# Sheet0-mcu.net
KiCad netlist of a schematic drawn in Altium Designer
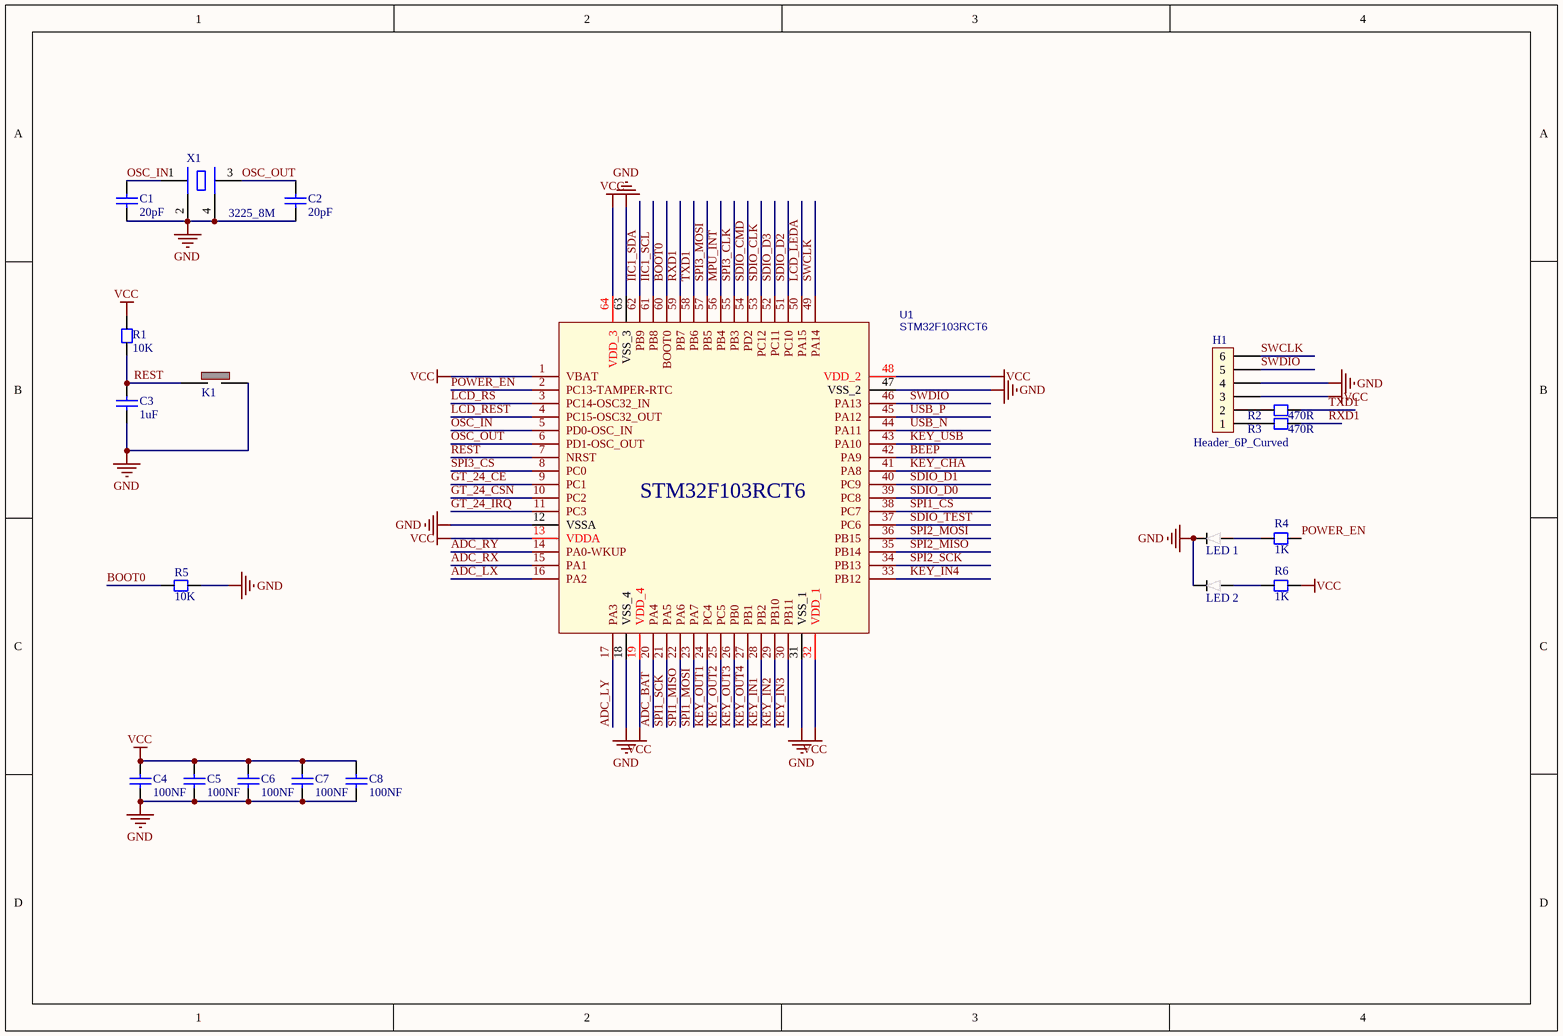
[diagram p0: Sheet0-mcu.SchDoc]

(export (version "E")
  (design (tool "Eeschema 10.0.6"))
  (components
    (comp (ref "C1")
      (value "20pF")
      (footprint "CC1608-0603")
      (description "0603封装的电容")
      (fields (field (name "PUBLISHER") "Altium Limited"))
      (libsource (lib "base") (part "Cap Chip 0603"))
    )
    (comp (ref "C2")
      (value "20pF")
      (footprint "CC1608-0603")
      (description "0603封装的电容")
      (fields (field (name "PUBLISHER") "Altium Limited"))
      (libsource (lib "base") (part "Cap Chip 0603"))
    )
    (comp (ref "C3")
      (value "1uF")
      (footprint "CC1608-0603")
      (description "0603封装的电容")
      (fields (field (name "PUBLISHER") "Altium Limited"))
      (libsource (lib "base") (part "Cap Chip 0603"))
    )
    (comp (ref "C4")
      (value "100NF")
      (footprint "CC1608-0603")
      (description "0603封装的电容")
      (fields (field (name "PUBLISHER") "Altium Limited"))
      (libsource (lib "base") (part "Cap Chip 0603"))
    )
    (comp (ref "C5")
      (value "100NF")
      (footprint "CC1608-0603")
      (description "0603封装的电容")
      (fields (field (name "PUBLISHER") "Altium Limited"))
      (libsource (lib "base") (part "Cap Chip 0603"))
    )
    (comp (ref "C6")
      (value "100NF")
      (footprint "CC1608-0603")
      (description "0603封装的电容")
      (fields (field (name "PUBLISHER") "Altium Limited"))
      (libsource (lib "base") (part "Cap Chip 0603"))
    )
    (comp (ref "C7")
      (value "100NF")
      (footprint "CC1608-0603")
      (description "0603封装的电容")
      (fields (field (name "PUBLISHER") "Altium Limited"))
      (libsource (lib "base") (part "Cap Chip 0603"))
    )
    (comp (ref "C8")
      (value "100NF")
      (footprint "CC1608-0603")
      (description "0603封装的电容")
      (fields (field (name "PUBLISHER") "Altium Limited"))
      (libsource (lib "base") (part "Cap Chip 0603"))
    )
    (comp (ref "H1")
      (value "Header_6P_Curved")
      (footprint "Header_2_54_6PW")
      (description "弯的6P排针")
      (libsource (lib "base") (part "Header_6P_Curved"))
    )
    (comp (ref "K1")
      (value "KEY 3*4")
      (footprint "KEY 3*4")
      (description "轻触开关按键")
      (libsource (lib "base") (part "KEY 3*4"))
    )
    (comp (ref "LED 1") (value "LED 0603") (footprint "LED 0603") (libsource (lib "base") (part "LED 0603")))
    (comp (ref "LED 2") (value "LED 0603") (footprint "LED 0603") (libsource (lib "base") (part "LED 0603")))
    (comp (ref "R1")
      (value "10K")
      (footprint "CR1608-0603")
      (description "0603封装电阻")
      (fields (field (name "PUBLISHER") "Altium Limited"))
      (libsource (lib "") (part "Resistor Chip 0603_1"))
    )
    (comp (ref "R2")
      (value "470R")
      (footprint "CR1608-0603")
      (description "贴片电阻")
      (libsource (lib "tianxiaohua_Schlib") (part "Chip resistor"))
    )
    (comp (ref "R3")
      (value "470R")
      (footprint "CR1608-0603")
      (description "贴片电阻")
      (libsource (lib "tianxiaohua_Schlib") (part "Chip resistor"))
    )
    (comp (ref "R4")
      (value "1K")
      (footprint "CR1608-0603")
      (description "0603封装电阻")
      (fields (field (name "PUBLISHER") "Altium Limited"))
      (libsource (lib "base") (part "Resistor Chip 0603"))
    )
    (comp (ref "R5")
      (value "10K")
      (footprint "CR1608-0603")
      (description "0603封装电阻")
      (fields (field (name "PUBLISHER") "Altium Limited"))
      (libsource (lib "base") (part "Resistor Chip 0603"))
    )
    (comp (ref "R6")
      (value "1K")
      (footprint "CR1608-0603")
      (description "0603封装电阻")
      (fields (field (name "PUBLISHER") "Altium Limited"))
      (libsource (lib "base") (part "Resistor Chip 0603"))
    )
    (comp (ref "U1")
      (value "STM32F103RCT6")
      (footprint "LQFP-64")
      (fields (field (name "BOM_SUPPLIER PART") "C8323"))
      (libsource (lib "singlechip") (part "STM32F103RCT6"))
    )
    (comp (ref "X1")
      (value "3225_8M")
      (footprint "XTAL-3225")
      (description "3225封装的晶振")
      (libsource (lib "base") (part "XTAL 3225"))
    )
  )
  (nets
    (net (code "1") (name "/ADC_BAT") (class "Default")
      (node (ref "U1") (pin "20") (pinfunction "PA4_20") (pintype "passive"))
    )
    (net (code "2") (name "/ADC_LX") (class "Default")
      (node (ref "U1") (pin "16") (pinfunction "PA2_16") (pintype "passive"))
    )
    (net (code "3") (name "/ADC_LY") (class "Default")
      (node (ref "U1") (pin "17") (pinfunction "PA3_17") (pintype "passive"))
    )
    (net (code "4") (name "/ADC_RX") (class "Default")
      (node (ref "U1") (pin "15") (pinfunction "PA1_15") (pintype "passive"))
    )
    (net (code "5") (name "/ADC_RY") (class "Default")
      (node (ref "U1") (pin "14") (pinfunction "PA0-WKUP_14") (pintype "passive"))
    )
    (net (code "6") (name "/BEEP") (class "Default")
      (node (ref "U1") (pin "42") (pinfunction "PA9_42") (pintype "passive"))
    )
    (net (code "7") (name "/BOOT0") (class "Default")
      (node (ref "R5") (pin "2") (pinfunction "2_2") (pintype "passive"))
      (node (ref "U1") (pin "60") (pinfunction "BOOT0_60") (pintype "passive"))
    )
    (net (code "8") (name "/GT_24_CE") (class "Default")
      (node (ref "U1") (pin "9") (pinfunction "PC1_9") (pintype "passive"))
    )
    (net (code "9") (name "/GT_24_CSN") (class "Default")
      (node (ref "U1") (pin "10") (pinfunction "PC2_10") (pintype "passive"))
    )
    (net (code "10") (name "/GT_24_IRQ") (class "Default")
      (node (ref "U1") (pin "11") (pinfunction "PC3_11") (pintype "passive"))
    )
    (net (code "11") (name "/IIC1_SCL") (class "Default")
      (node (ref "U1") (pin "61") (pinfunction "PB8_61") (pintype "passive"))
    )
    (net (code "12") (name "/IIC1_SDA") (class "Default")
      (node (ref "U1") (pin "62") (pinfunction "PB9_62") (pintype "passive"))
    )
    (net (code "13") (name "/KEY_CHA") (class "Default")
      (node (ref "U1") (pin "41") (pinfunction "PA8_41") (pintype "passive"))
    )
    (net (code "14") (name "/KEY_IN1") (class "Default")
      (node (ref "U1") (pin "28") (pinfunction "PB2_28") (pintype "passive"))
    )
    (net (code "15") (name "/KEY_IN2") (class "Default")
      (node (ref "U1") (pin "29") (pinfunction "PB10_29") (pintype "passive"))
    )
    (net (code "16") (name "/KEY_IN3") (class "Default")
      (node (ref "U1") (pin "30") (pinfunction "PB11_30") (pintype "passive"))
    )
    (net (code "17") (name "/KEY_IN4") (class "Default")
      (node (ref "U1") (pin "33") (pinfunction "PB12_33") (pintype "passive"))
    )
    (net (code "18") (name "/KEY_OUT1") (class "Default")
      (node (ref "U1") (pin "24") (pinfunction "PC4_24") (pintype "passive"))
    )
    (net (code "19") (name "/KEY_OUT2") (class "Default")
      (node (ref "U1") (pin "25") (pinfunction "PC5_25") (pintype "passive"))
    )
    (net (code "20") (name "/KEY_OUT3") (class "Default")
      (node (ref "U1") (pin "26") (pinfunction "PB0_26") (pintype "passive"))
    )
    (net (code "21") (name "/KEY_OUT4") (class "Default")
      (node (ref "U1") (pin "27") (pinfunction "PB1_27") (pintype "passive"))
    )
    (net (code "22") (name "/KEY_USB") (class "Default")
      (node (ref "U1") (pin "43") (pinfunction "PA10_43") (pintype "passive"))
    )
    (net (code "23") (name "/LCD_LEDA") (class "Default")
      (node (ref "U1") (pin "50") (pinfunction "PA15_50") (pintype "passive"))
    )
    (net (code "24") (name "/LCD_REST") (class "Default")
      (node (ref "U1") (pin "4") (pinfunction "PC15-OSC32_OUT_4") (pintype "passive"))
    )
    (net (code "25") (name "/LCD_RS") (class "Default")
      (node (ref "U1") (pin "3") (pinfunction "PC14-OSC32_IN_3") (pintype "passive"))
    )
    (net (code "26") (name "/MPU_INT") (class "Default")
      (node (ref "U1") (pin "56") (pinfunction "PB4_56") (pintype "passive"))
    )
    (net (code "27") (name "/OSC_IN") (class "Default")
      (node (ref "C1") (pin "2") (pinfunction "2_2") (pintype "passive"))
      (node (ref "U1") (pin "5") (pinfunction "PD0-OSC_IN_5") (pintype "passive"))
      (node (ref "X1") (pin "1") (pinfunction "OSC1_1") (pintype "passive"))
    )
    (net (code "28") (name "/OSC_OUT") (class "Default")
      (node (ref "C2") (pin "2") (pinfunction "2_2") (pintype "passive"))
      (node (ref "U1") (pin "6") (pinfunction "PD1-OSC_OUT_6") (pintype "passive"))
      (node (ref "X1") (pin "3") (pinfunction "OSC2_3") (pintype "passive"))
    )
    (net (code "29") (name "/POWER_EN") (class "Default")
      (node (ref "R4") (pin "1") (pinfunction "1_1") (pintype "passive"))
      (node (ref "U1") (pin "2") (pinfunction "PC13-TAMPER-RTC_2") (pintype "passive"))
    )
    (net (code "30") (name "/REST") (class "Default")
      (node (ref "C3") (pin "2") (pinfunction "2_2") (pintype "passive"))
      (node (ref "K1") (pin "1") (pinfunction "1_1") (pintype "passive"))
      (node (ref "R1") (pin "1") (pinfunction "1_1") (pintype "passive"))
      (node (ref "U1") (pin "7") (pinfunction "NRST_7") (pintype "passive"))
    )
    (net (code "31") (name "/RXD1") (class "Default")
      (node (ref "R3") (pin "1") (pinfunction "1_1") (pintype "passive"))
      (node (ref "U1") (pin "59") (pinfunction "PB7_59") (pintype "passive"))
    )
    (net (code "32") (name "/SDIO_CLK") (class "Default")
      (node (ref "U1") (pin "53") (pinfunction "PC12_53") (pintype "passive"))
    )
    (net (code "33") (name "/SDIO_CMD") (class "Default")
      (node (ref "U1") (pin "54") (pinfunction "PD2_54") (pintype "passive"))
    )
    (net (code "34") (name "/SDIO_D0") (class "Default")
      (node (ref "U1") (pin "39") (pinfunction "PC8_39") (pintype "passive"))
    )
    (net (code "35") (name "/SDIO_D1") (class "Default")
      (node (ref "U1") (pin "40") (pinfunction "PC9_40") (pintype "passive"))
    )
    (net (code "36") (name "/SDIO_D2") (class "Default")
      (node (ref "U1") (pin "51") (pinfunction "PC10_51") (pintype "passive"))
    )
    (net (code "37") (name "/SDIO_D3") (class "Default")
      (node (ref "U1") (pin "52") (pinfunction "PC11_52") (pintype "passive"))
    )
    (net (code "38") (name "/SDIO_TEST") (class "Default")
      (node (ref "U1") (pin "37") (pinfunction "PC6_37") (pintype "passive"))
    )
    (net (code "39") (name "/SPI1_CS") (class "Default")
      (node (ref "U1") (pin "38") (pinfunction "PC7_38") (pintype "passive"))
    )
    (net (code "40") (name "/SPI1_MISO") (class "Default")
      (node (ref "U1") (pin "22") (pinfunction "PA6_22") (pintype "passive"))
    )
    (net (code "41") (name "/SPI1_MOSI") (class "Default")
      (node (ref "U1") (pin "23") (pinfunction "PA7_23") (pintype "passive"))
    )
    (net (code "42") (name "/SPI1_SCK") (class "Default")
      (node (ref "U1") (pin "21") (pinfunction "PA5_21") (pintype "passive"))
    )
    (net (code "43") (name "/SPI2_MISO") (class "Default")
      (node (ref "U1") (pin "35") (pinfunction "PB14_35") (pintype "passive"))
    )
    (net (code "44") (name "/SPI2_MOSI") (class "Default")
      (node (ref "U1") (pin "36") (pinfunction "PB15_36") (pintype "passive"))
    )
    (net (code "45") (name "/SPI2_SCK") (class "Default")
      (node (ref "U1") (pin "34") (pinfunction "PB13_34") (pintype "passive"))
    )
    (net (code "46") (name "/SPI3_CLK") (class "Default")
      (node (ref "U1") (pin "55") (pinfunction "PB3_55") (pintype "passive"))
    )
    (net (code "47") (name "/SPI3_CS") (class "Default")
      (node (ref "U1") (pin "8") (pinfunction "PC0_8") (pintype "passive"))
    )
    (net (code "48") (name "/SPI3_MOSI") (class "Default")
      (node (ref "U1") (pin "57") (pinfunction "PB5_57") (pintype "passive"))
    )
    (net (code "49") (name "/SWCLK") (class "Default")
      (node (ref "H1") (pin "6") (pinfunction "6_6") (pintype "passive"))
      (node (ref "U1") (pin "49") (pinfunction "PA14_49") (pintype "passive"))
    )
    (net (code "50") (name "/SWDIO") (class "Default")
      (node (ref "H1") (pin "5") (pinfunction "5_5") (pintype "passive"))
      (node (ref "U1") (pin "46") (pinfunction "PA13_46") (pintype "passive"))
    )
    (net (code "51") (name "/TXD1") (class "Default")
      (node (ref "R2") (pin "1") (pinfunction "1_1") (pintype "passive"))
      (node (ref "U1") (pin "58") (pinfunction "PB6_58") (pintype "passive"))
    )
    (net (code "52") (name "/USB_N") (class "Default")
      (node (ref "U1") (pin "44") (pinfunction "PA11_44") (pintype "passive"))
    )
    (net (code "53") (name "/USB_P") (class "Default")
      (node (ref "U1") (pin "45") (pinfunction "PA12_45") (pintype "passive"))
    )
    (net (code "54") (name "GND") (class "Default")
      (node (ref "C1") (pin "1") (pinfunction "1_1") (pintype "passive"))
      (node (ref "C2") (pin "1") (pinfunction "1_1") (pintype "passive"))
      (node (ref "C3") (pin "1") (pinfunction "1_1") (pintype "passive"))
      (node (ref "C4") (pin "1") (pinfunction "1_1") (pintype "passive"))
      (node (ref "C5") (pin "1") (pinfunction "1_1") (pintype "passive"))
      (node (ref "C6") (pin "1") (pinfunction "1_1") (pintype "passive"))
      (node (ref "C7") (pin "1") (pinfunction "1_1") (pintype "passive"))
      (node (ref "C8") (pin "1") (pinfunction "1_1") (pintype "passive"))
      (node (ref "H1") (pin "4") (pinfunction "4_4") (pintype "passive"))
      (node (ref "K1") (pin "2") (pinfunction "2_2") (pintype "passive"))
      (node (ref "LED 1") (pin "2") (pinfunction "2_2") (pintype "passive"))
      (node (ref "LED 2") (pin "2") (pinfunction "2_2") (pintype "passive"))
      (node (ref "R5") (pin "1") (pinfunction "1_1") (pintype "passive"))
      (node (ref "U1") (pin "12") (pinfunction "VSSA_12") (pintype "passive"))
      (node (ref "U1") (pin "18") (pinfunction "VSS_4_18") (pintype "passive"))
      (node (ref "U1") (pin "31") (pinfunction "VSS_1_31") (pintype "passive"))
      (node (ref "U1") (pin "47") (pinfunction "VSS_2_47") (pintype "passive"))
      (node (ref "U1") (pin "63") (pinfunction "VSS_3_63") (pintype "passive"))
      (node (ref "X1") (pin "2") (pinfunction "GND_2") (pintype "passive"))
      (node (ref "X1") (pin "4") (pinfunction "GND_4") (pintype "passive"))
    )
    (net (code "55") (name "Net-(H1-Pad1)") (class "Default")
      (node (ref "H1") (pin "1") (pinfunction "1_1") (pintype "passive"))
      (node (ref "R3") (pin "2") (pinfunction "2_2") (pintype "passive"))
    )
    (net (code "56") (name "Net-(H1-Pad2)") (class "Default")
      (node (ref "H1") (pin "2") (pinfunction "2_2") (pintype "passive"))
      (node (ref "R2") (pin "2") (pinfunction "2_2") (pintype "passive"))
    )
    (net (code "57") (name "Net-(LED 1-Pad1)") (class "Default")
      (node (ref "LED 1") (pin "1") (pinfunction "1_1") (pintype "passive"))
      (node (ref "R4") (pin "2") (pinfunction "2_2") (pintype "passive"))
    )
    (net (code "58") (name "Net-(LED 2-Pad1)") (class "Default")
      (node (ref "LED 2") (pin "1") (pinfunction "1_1") (pintype "passive"))
      (node (ref "R6") (pin "2") (pinfunction "2_2") (pintype "passive"))
    )
    (net (code "59") (name "VCC") (class "Default")
      (node (ref "C4") (pin "2") (pinfunction "2_2") (pintype "passive"))
      (node (ref "C5") (pin "2") (pinfunction "2_2") (pintype "passive"))
      (node (ref "C6") (pin "2") (pinfunction "2_2") (pintype "passive"))
      (node (ref "C7") (pin "2") (pinfunction "2_2") (pintype "passive"))
      (node (ref "C8") (pin "2") (pinfunction "2_2") (pintype "passive"))
      (node (ref "H1") (pin "3") (pinfunction "3_3") (pintype "passive"))
      (node (ref "R1") (pin "2") (pinfunction "2_2") (pintype "passive"))
      (node (ref "R6") (pin "1") (pinfunction "1_1") (pintype "passive"))
      (node (ref "U1") (pin "1") (pinfunction "VBAT_1") (pintype "passive"))
      (node (ref "U1") (pin "13") (pinfunction "VDDA_13") (pintype "passive"))
      (node (ref "U1") (pin "19") (pinfunction "VDD_4_19") (pintype "passive"))
      (node (ref "U1") (pin "32") (pinfunction "VDD_1_32") (pintype "passive"))
      (node (ref "U1") (pin "48") (pinfunction "VDD_2_48") (pintype "passive"))
      (node (ref "U1") (pin "64") (pinfunction "VDD_3_64") (pintype "passive"))
    )
  )
)
